# Realtime_EEPROM.net
KiCad netlist of a schematic drawn in Altium Designer
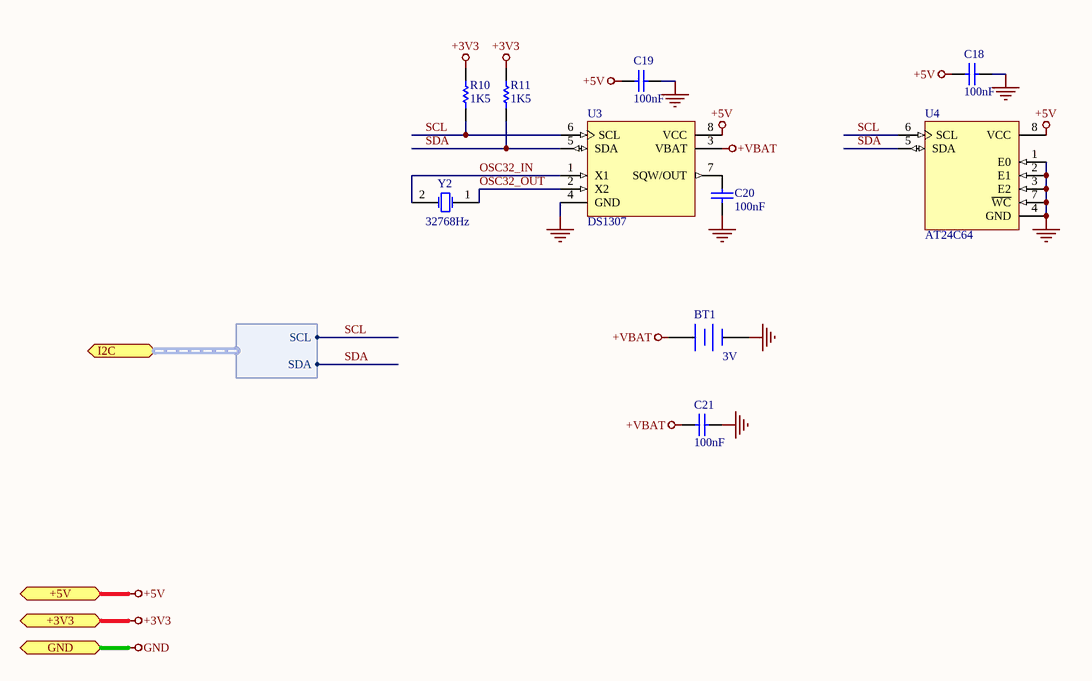
[diagram p0: Realtime&EEPROM.SchDoc]

(export (version "E")
  (design (tool "Eeschema 10.0.6"))
  (components
    (comp (ref "BT1")
      (value "3V")
      (footprint "SK-BATT-CR1220")
      (description "Multicell Battery")
      (fields (field (name "Comment") "CR1220"))
      (libsource (lib "Miscellaneous Devices") (part "Battery"))
    )
    (comp (ref "C18")
      (value "100nF")
      (footprint "C-0805")
      (description "Capacitor")
      (fields (field (name "Comment") "104") (field (name "PUBLISHER") "Altium Limited"))
      (libsource (lib "Miscellaneous Devices") (part "Cap"))
    )
    (comp (ref "C19")
      (value "100nF")
      (footprint "C-0805")
      (description "Capacitor")
      (fields (field (name "Comment") "104") (field (name "PUBLISHER") "Altium Limited"))
      (libsource (lib "Miscellaneous Devices") (part "Cap"))
    )
    (comp (ref "C20")
      (value "100nF")
      (footprint "C-0805")
      (description "Capacitor")
      (fields (field (name "Comment") "104") (field (name "PUBLISHER") "Altium Limited"))
      (libsource (lib "Miscellaneous Devices") (part "Cap"))
    )
    (comp (ref "C21")
      (value "100nF")
      (footprint "C-0805")
      (description "Capacitor")
      (fields (field (name "Comment") "104") (field (name "PUBLISHER") "Altium Limited"))
      (libsource (lib "Miscellaneous Devices") (part "Cap"))
    )
    (comp (ref "R10")
      (value "1K5")
      (footprint "R-0805")
      (description "Resistor")
      (fields (field (name "PUBLISHER") "Altium Limited"))
      (libsource (lib "Miscellaneous Devices") (part "Res1"))
    )
    (comp (ref "R11")
      (value "1K5")
      (footprint "R-0805")
      (description "Resistor")
      (fields (field (name "PUBLISHER") "Altium Limited"))
      (libsource (lib "Miscellaneous Devices") (part "Res1"))
    )
    (comp (ref "U3")
      (value "DS1307")
      (footprint "SOIC-8")
      (description "64 X 8 Serial Real-Time Clock")
      (libsource (lib "Dallas Peripheral Real Time Clock") (part "DS1307"))
    )
    (comp (ref "U4")
      (value "AT24C64")
      (footprint "SOIC-8")
      (description "64 Kbit Serial I²C Bus EEPROM")
      (libsource (lib "ST Memory EEPROM Serial") (part "M24C64BN1"))
    )
    (comp (ref "Y2")
      (value "32768Hz")
      (footprint "XTAL-AB38T-SMD")
      (description "Crystal Oscillator")
      (libsource (lib "Miscellaneous Devices") (part "XTAL"))
    )
  )
  (nets
    (net (code "2") (name "+3V3") (class "Default")
      (node (ref "R10") (pin "2") (pinfunction "2_2") (pintype "passive"))
      (node (ref "R11") (pin "2") (pinfunction "2_2") (pintype "passive"))
    )
    (net (code "3") (name "+5V") (class "Default")
      (node (ref "C18") (pin "1") (pinfunction "1_1") (pintype "passive"))
      (node (ref "C19") (pin "1") (pinfunction "1_1") (pintype "passive"))
      (node (ref "U3") (pin "8") (pinfunction "VCC_8") (pintype "power_in"))
      (node (ref "U4") (pin "8") (pinfunction "VCC_8") (pintype "power_in"))
    )
    (net (code "4") (name "+VBAT") (class "Default")
      (node (ref "BT1") (pin "1") (pinfunction "+_1") (pintype "passive"))
      (node (ref "C21") (pin "1") (pinfunction "1_1") (pintype "passive"))
      (node (ref "U3") (pin "3") (pinfunction "VBAT_3") (pintype "power_in"))
    )
    (net (code "5") (name "/OSC32_IN") (class "Default")
      (node (ref "U3") (pin "1") (pinfunction "X1_1") (pintype "input"))
      (node (ref "Y2") (pin "2") (pinfunction "OSC2_2") (pintype "passive"))
    )
    (net (code "6") (name "/OSC32_OUT") (class "Default")
      (node (ref "U3") (pin "2") (pinfunction "X2_2") (pintype "input"))
      (node (ref "Y2") (pin "1") (pinfunction "OSC1_1") (pintype "passive"))
    )
    (net (code "7") (name "/SCL") (class "Default")
      (node (ref "R10") (pin "1") (pinfunction "1_1") (pintype "passive"))
      (node (ref "U3") (pin "6") (pinfunction "SCL_6") (pintype "input"))
      (node (ref "U4") (pin "6") (pinfunction "SCL_6") (pintype "input"))
    )
    (net (code "8") (name "/SDA") (class "Default")
      (node (ref "R11") (pin "1") (pinfunction "1_1") (pintype "passive"))
      (node (ref "U3") (pin "5") (pinfunction "SDA_5") (pintype "bidirectional"))
      (node (ref "U4") (pin "5") (pinfunction "SDA_5") (pintype "bidirectional"))
    )
    (net (code "10") (name "GND") (class "Default")
      (node (ref "BT1") (pin "2") (pinfunction "-_2") (pintype "passive"))
      (node (ref "C18") (pin "2") (pinfunction "2_2") (pintype "passive"))
      (node (ref "C19") (pin "2") (pinfunction "2_2") (pintype "passive"))
      (node (ref "C20") (pin "2") (pinfunction "2_2") (pintype "passive"))
      (node (ref "C21") (pin "2") (pinfunction "2_2") (pintype "passive"))
      (node (ref "U3") (pin "4") (pinfunction "GND_4") (pintype "power_in"))
      (node (ref "U4") (pin "1") (pinfunction "E0_1") (pintype "input"))
      (node (ref "U4") (pin "2") (pinfunction "E1_2") (pintype "input"))
      (node (ref "U4") (pin "3") (pinfunction "E2_3") (pintype "input"))
      (node (ref "U4") (pin "4") (pinfunction "GND_4") (pintype "power_in"))
      (node (ref "U4") (pin "7") (pinfunction "~{WC}_7") (pintype "input"))
    )
    (net (code "11") (name "Net-(U3-SQW{slash}OUT)") (class "Default")
      (node (ref "C20") (pin "1") (pinfunction "1_1") (pintype "passive"))
      (node (ref "U3") (pin "7") (pinfunction "SQW/OUT_7") (pintype "output"))
    )
  )
)
